# spin_pov_LDO.net
KiCad netlist of a schematic drawn in EAGLE
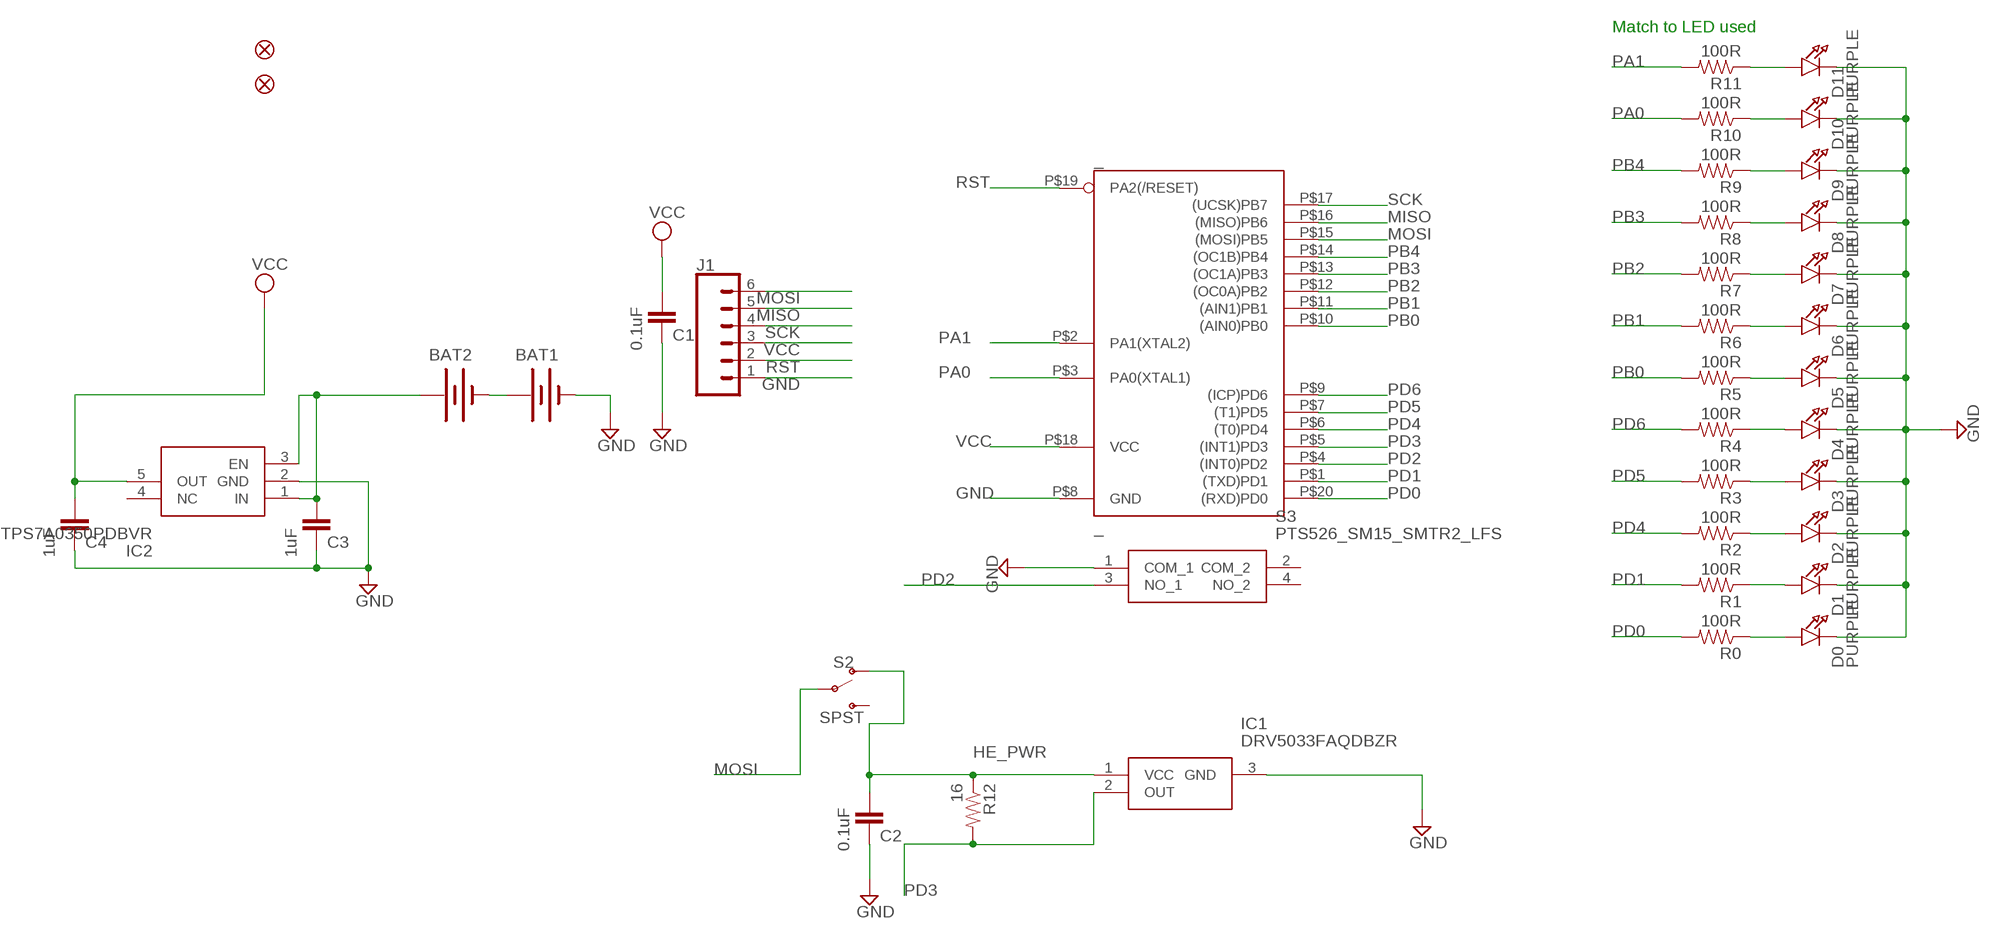
[diagram p0: schematic, sheet 1]

(export (version "E")
  (design (tool "Eeschema 10.0.6"))
  (components
    (comp (ref "AFID1")
      (value "FIDUCIAL\"\"")
      (footprint "eagle-import:FIDUCIAL_1MM")
      (libsource (lib "eagle-import") (part "FIDUCIAL{dblquote}{dblquote}"))
    )
    (comp (ref "AFID2")
      (value "FIDUCIAL\"\"")
      (footprint "eagle-import:FIDUCIAL_1MM")
      (libsource (lib "eagle-import") (part "FIDUCIAL{dblquote}{dblquote}"))
    )
    (comp (ref "BAT1")
      (value "SPARKFUN_BATTERYSPARKFUN_BATTCOMM_20MM_LINX")
      (footprint "eagle-import:SPARKFUN_BATTCOM_20MM_LINX")
      (libsource (lib "eagle-import") (part "SPARKFUN_BATTERYSPARKFUN_BATTCOMM_20MM_LINX"))
    )
    (comp (ref "BAT2")
      (value "SPARKFUN_BATTERYSPARKFUN_BATTCOMM_20MM_LINX")
      (footprint "eagle-import:SPARKFUN_BATTCOM_20MM_LINX")
      (libsource (lib "eagle-import") (part "SPARKFUN_BATTERYSPARKFUN_BATTCOMM_20MM_LINX"))
    )
    (comp (ref "C1")
      (value "0.1uF")
      (footprint "eagle-import:0805")
      (libsource (lib "eagle-import") (part "CAP0805"))
    )
    (comp (ref "C2")
      (value "0.1uF")
      (footprint "eagle-import:0805")
      (libsource (lib "eagle-import") (part "CAP0805"))
    )
    (comp (ref "C3")
      (value "1uF")
      (footprint "eagle-import:0805")
      (libsource (lib "eagle-import") (part "CAP0805"))
    )
    (comp (ref "C4")
      (value "1uF")
      (footprint "eagle-import:0805")
      (libsource (lib "eagle-import") (part "CAP0805"))
    )
    (comp (ref "D0")
      (value "PURPLE")
      (footprint "eagle-import:CHIPLED_0805_NOOUTLINE")
      (libsource (lib "eagle-import") (part "LED0805_NOOUTLINE"))
    )
    (comp (ref "D1")
      (value "PURPLE")
      (footprint "eagle-import:CHIPLED_0805_NOOUTLINE")
      (libsource (lib "eagle-import") (part "LED0805_NOOUTLINE"))
    )
    (comp (ref "D2")
      (value "PURPLE")
      (footprint "eagle-import:CHIPLED_0805_NOOUTLINE")
      (libsource (lib "eagle-import") (part "LED0805_NOOUTLINE"))
    )
    (comp (ref "D3")
      (value "PURPLE")
      (footprint "eagle-import:CHIPLED_0805_NOOUTLINE")
      (libsource (lib "eagle-import") (part "LED0805_NOOUTLINE"))
    )
    (comp (ref "D4")
      (value "PURPLE")
      (footprint "eagle-import:CHIPLED_0805_NOOUTLINE")
      (libsource (lib "eagle-import") (part "LED0805_NOOUTLINE"))
    )
    (comp (ref "D5")
      (value "PURPLE")
      (footprint "eagle-import:CHIPLED_0805_NOOUTLINE")
      (libsource (lib "eagle-import") (part "LED0805_NOOUTLINE"))
    )
    (comp (ref "D6")
      (value "PURPLE")
      (footprint "eagle-import:CHIPLED_0805_NOOUTLINE")
      (libsource (lib "eagle-import") (part "LED0805_NOOUTLINE"))
    )
    (comp (ref "D7")
      (value "PURPLE")
      (footprint "eagle-import:CHIPLED_0805_NOOUTLINE")
      (libsource (lib "eagle-import") (part "LED0805_NOOUTLINE"))
    )
    (comp (ref "D8")
      (value "PURPLE")
      (footprint "eagle-import:CHIPLED_0805_NOOUTLINE")
      (libsource (lib "eagle-import") (part "LED0805_NOOUTLINE"))
    )
    (comp (ref "D9")
      (value "PURPLE")
      (footprint "eagle-import:CHIPLED_0805_NOOUTLINE")
      (libsource (lib "eagle-import") (part "LED0805_NOOUTLINE"))
    )
    (comp (ref "D10")
      (value "PURPLE")
      (footprint "eagle-import:CHIPLED_0805_NOOUTLINE")
      (libsource (lib "eagle-import") (part "LED0805_NOOUTLINE"))
    )
    (comp (ref "D11")
      (value "PURPLE")
      (footprint "eagle-import:CHIPLED_0805_NOOUTLINE")
      (libsource (lib "eagle-import") (part "LED0805_NOOUTLINE"))
    )
    (comp (ref "IC1")
      (value "DRV5033FAQDBZR")
      (footprint "eagle-import:SOT95P237X112-3N")
      (fields (field (name "MOUSER_PART_NUMBER") "595-DRV5033FAQDBZR"))
      (libsource (lib "eagle-import") (part "DRV5033FAQDBZR"))
    )
    (comp (ref "IC2")
      (value "TPS7A0350PDBVR")
      (footprint "eagle-import:SOT95P280X145-5N")
      (fields (field (name "MOUSER_PART_NUMBER") "595-TPS7A0350PDBVR"))
      (libsource (lib "eagle-import") (part "TPS7A0350PDBVR"))
    )
    (comp (ref "J1")
      (value "CONN_06SMD-FEMALE-V2")
      (footprint "eagle-import:1X06-SMD-FEMALE")
      (libsource (lib "eagle-import") (part "CONN_06SMD-FEMALE-V2"))
    )
    (comp (ref "R0")
      (value "100R")
      (footprint "eagle-import:0805")
      (fields (field (name "SPICEPREFIX") "R"))
      (libsource (lib "eagle-import") (part "RESISTOR"))
    )
    (comp (ref "R1")
      (value "100R")
      (footprint "eagle-import:0805")
      (libsource (lib "eagle-import") (part "RESISTOR"))
    )
    (comp (ref "R2")
      (value "100R")
      (footprint "eagle-import:0805")
      (libsource (lib "eagle-import") (part "RESISTOR"))
    )
    (comp (ref "R3")
      (value "100R")
      (footprint "eagle-import:0805")
      (libsource (lib "eagle-import") (part "RESISTOR"))
    )
    (comp (ref "R4")
      (value "100R")
      (footprint "eagle-import:0805")
      (libsource (lib "eagle-import") (part "RESISTOR"))
    )
    (comp (ref "R5")
      (value "100R")
      (footprint "eagle-import:0805")
      (libsource (lib "eagle-import") (part "RESISTOR"))
    )
    (comp (ref "R6")
      (value "100R")
      (footprint "eagle-import:0805")
      (libsource (lib "eagle-import") (part "RESISTOR"))
    )
    (comp (ref "R7")
      (value "100R")
      (footprint "eagle-import:0805")
      (libsource (lib "eagle-import") (part "RESISTOR"))
    )
    (comp (ref "R8")
      (value "100R")
      (footprint "eagle-import:0805")
      (libsource (lib "eagle-import") (part "RESISTOR"))
    )
    (comp (ref "R9")
      (value "100R")
      (footprint "eagle-import:0805")
      (libsource (lib "eagle-import") (part "RESISTOR"))
    )
    (comp (ref "R10")
      (value "100R")
      (footprint "eagle-import:0805")
      (libsource (lib "eagle-import") (part "RESISTOR"))
    )
    (comp (ref "R11")
      (value "100R")
      (footprint "eagle-import:0805")
      (libsource (lib "eagle-import") (part "RESISTOR"))
    )
    (comp (ref "R12")
      (value "16")
      (footprint "eagle-import:0805")
      (libsource (lib "eagle-import") (part "RESISTOR"))
    )
    (comp (ref "S2")
      (value "SPST")
      (footprint "eagle-import:SWITCH_SPST_SMD_A")
      (libsource (lib "eagle-import") (part "SWITCH-SPDT-SMD-RIGHT-ANGLE"))
    )
    (comp (ref "S3")
      (value "PTS526_SM15_SMTR2_LFS")
      (footprint "eagle-import:PTS526SM15SMTR2LFS")
      (fields
        (field (name "MANUFACTURER_PART_NUMBER") "PTS526 SM15 SMTR2 LFS")
        (field (name "MOUSER_PART_NUMBER") "611-PTS526SM15SMTR2L")
      )
      (libsource (lib "eagle-import") (part "PTS526_SM15_SMTR2_LFS"))
    )
    (comp (ref "_")
      (value "_")
      (footprint "eagle-import:MLF20")
      (libsource (lib "eagle-import") (part "TINY2313-M"))
    )
  )
  (nets
    (net (code "1") (name "/HE_PWR") (class "Default")
      (node (ref "C2") (pin "1") (pinfunction "1_1") (pintype "passive"))
      (node (ref "IC1") (pin "1") (pinfunction "VCC_1") (pintype "bidirectional"))
      (node (ref "R12") (pin "1") (pinfunction "1_1") (pintype "passive"))
      (node (ref "S2") (pin "1") (pinfunction "O_1") (pintype "passive"))
    )
    (net (code "2") (name "/MISO") (class "Default")
      (node (ref "J1") (pin "5") (pinfunction "5_5") (pintype "passive"))
      (node (ref "_") (pin "P$16") (pinfunction "(MISO)PB6_P$16") (pintype "bidirectional"))
    )
    (net (code "3") (name "/MOSI") (class "Default")
      (node (ref "J1") (pin "6") (pinfunction "6_6") (pintype "passive"))
      (node (ref "S2") (pin "2") (pinfunction "P_2") (pintype "passive"))
      (node (ref "_") (pin "P$15") (pinfunction "(MOSI)PB5_P$15") (pintype "bidirectional"))
    )
    (net (code "4") (name "/PA0") (class "Default")
      (node (ref "R10") (pin "2") (pinfunction "2_2") (pintype "passive"))
      (node (ref "_") (pin "P$3") (pinfunction "PA0(XTAL1)_P$3") (pintype "bidirectional"))
    )
    (net (code "5") (name "/PA1") (class "Default")
      (node (ref "R11") (pin "2") (pinfunction "2_2") (pintype "passive"))
      (node (ref "_") (pin "P$2") (pinfunction "PA1(XTAL2)_P$2") (pintype "bidirectional"))
    )
    (net (code "6") (name "/PB0") (class "Default")
      (node (ref "R5") (pin "2") (pinfunction "2_2") (pintype "passive"))
      (node (ref "_") (pin "P$10") (pinfunction "(AIN0)PB0_P$10") (pintype "bidirectional"))
    )
    (net (code "7") (name "/PB1") (class "Default")
      (node (ref "R6") (pin "2") (pinfunction "2_2") (pintype "passive"))
      (node (ref "_") (pin "P$11") (pinfunction "(AIN1)PB1_P$11") (pintype "bidirectional"))
    )
    (net (code "8") (name "/PB2") (class "Default")
      (node (ref "R7") (pin "2") (pinfunction "2_2") (pintype "passive"))
      (node (ref "_") (pin "P$12") (pinfunction "(OC0A)PB2_P$12") (pintype "bidirectional"))
    )
    (net (code "9") (name "/PB3") (class "Default")
      (node (ref "R8") (pin "2") (pinfunction "2_2") (pintype "passive"))
      (node (ref "_") (pin "P$13") (pinfunction "(OC1A)PB3_P$13") (pintype "bidirectional"))
    )
    (net (code "10") (name "/PB4") (class "Default")
      (node (ref "R9") (pin "2") (pinfunction "2_2") (pintype "passive"))
      (node (ref "_") (pin "P$14") (pinfunction "(OC1B)PB4_P$14") (pintype "bidirectional"))
    )
    (net (code "11") (name "/PD0") (class "Default")
      (node (ref "R0") (pin "2") (pinfunction "2_2") (pintype "passive"))
      (node (ref "_") (pin "P$20") (pinfunction "(RXD)PD0_P$20") (pintype "bidirectional"))
    )
    (net (code "12") (name "/PD1") (class "Default")
      (node (ref "R1") (pin "2") (pinfunction "2_2") (pintype "passive"))
      (node (ref "_") (pin "P$1") (pinfunction "(TXD)PD1_P$1") (pintype "bidirectional"))
    )
    (net (code "13") (name "/PD2") (class "Default")
      (node (ref "S3") (pin "3") (pinfunction "NO_1_3") (pintype "bidirectional"))
      (node (ref "_") (pin "P$4") (pinfunction "(INT0)PD2_P$4") (pintype "bidirectional"))
    )
    (net (code "14") (name "/PD3") (class "Default")
      (node (ref "IC1") (pin "2") (pinfunction "OUT_2") (pintype "bidirectional"))
      (node (ref "R12") (pin "2") (pinfunction "2_2") (pintype "passive"))
      (node (ref "_") (pin "P$5") (pinfunction "(INT1)PD3_P$5") (pintype "bidirectional"))
    )
    (net (code "15") (name "/PD4") (class "Default")
      (node (ref "R2") (pin "2") (pinfunction "2_2") (pintype "passive"))
      (node (ref "_") (pin "P$6") (pinfunction "(T0)PD4_P$6") (pintype "bidirectional"))
    )
    (net (code "16") (name "/PD5") (class "Default")
      (node (ref "R3") (pin "2") (pinfunction "2_2") (pintype "passive"))
      (node (ref "_") (pin "P$7") (pinfunction "(T1)PD5_P$7") (pintype "bidirectional"))
    )
    (net (code "17") (name "/PD6") (class "Default")
      (node (ref "R4") (pin "2") (pinfunction "2_2") (pintype "passive"))
      (node (ref "_") (pin "P$9") (pinfunction "(ICP)PD6_P$9") (pintype "bidirectional"))
    )
    (net (code "18") (name "/RST") (class "Default")
      (node (ref "J1") (pin "2") (pinfunction "2_2") (pintype "passive"))
      (node (ref "_") (pin "P$19") (pinfunction "PA2(/RESET)_P$19") (pintype "input"))
    )
    (net (code "19") (name "/SCK") (class "Default")
      (node (ref "J1") (pin "4") (pinfunction "4_4") (pintype "passive"))
      (node (ref "_") (pin "P$17") (pinfunction "(UCSK)PB7_P$17") (pintype "bidirectional"))
    )
    (net (code "20") (name "GND") (class "Default")
      (node (ref "BAT1") (pin "2") (pinfunction "-_2") (pintype "power_in"))
      (node (ref "C1") (pin "2") (pinfunction "2_2") (pintype "passive"))
      (node (ref "C2") (pin "2") (pinfunction "2_2") (pintype "passive"))
      (node (ref "C3") (pin "2") (pinfunction "2_2") (pintype "passive"))
      (node (ref "C4") (pin "2") (pinfunction "2_2") (pintype "passive"))
      (node (ref "D0") (pin "C") (pinfunction "C_C") (pintype "passive"))
      (node (ref "D1") (pin "C") (pinfunction "C_C") (pintype "passive"))
      (node (ref "D10") (pin "C") (pinfunction "C_C") (pintype "passive"))
      (node (ref "D11") (pin "C") (pinfunction "C_C") (pintype "passive"))
      (node (ref "D2") (pin "C") (pinfunction "C_C") (pintype "passive"))
      (node (ref "D3") (pin "C") (pinfunction "C_C") (pintype "passive"))
      (node (ref "D4") (pin "C") (pinfunction "C_C") (pintype "passive"))
      (node (ref "D5") (pin "C") (pinfunction "C_C") (pintype "passive"))
      (node (ref "D6") (pin "C") (pinfunction "C_C") (pintype "passive"))
      (node (ref "D7") (pin "C") (pinfunction "C_C") (pintype "passive"))
      (node (ref "D8") (pin "C") (pinfunction "C_C") (pintype "passive"))
      (node (ref "D9") (pin "C") (pinfunction "C_C") (pintype "passive"))
      (node (ref "IC1") (pin "3") (pinfunction "GND_3") (pintype "bidirectional"))
      (node (ref "IC2") (pin "2") (pinfunction "GND_2") (pintype "bidirectional"))
      (node (ref "J1") (pin "1") (pinfunction "1_1") (pintype "passive"))
      (node (ref "S3") (pin "1") (pinfunction "COM_1_1") (pintype "bidirectional"))
      (node (ref "_") (pin "P$8") (pinfunction "GND_P$8") (pintype "power_in"))
    )
    (net (code "21") (name "Net-(BAT1-+)") (class "Default")
      (node (ref "BAT1") (pin "1") (pinfunction "+_1") (pintype "power_in"))
      (node (ref "BAT2") (pin "2") (pinfunction "-_2") (pintype "power_in"))
    )
    (net (code "22") (name "Net-(BAT2-+)") (class "Default")
      (node (ref "BAT2") (pin "1") (pinfunction "+_1") (pintype "power_in"))
      (node (ref "C3") (pin "1") (pinfunction "1_1") (pintype "passive"))
      (node (ref "IC2") (pin "1") (pinfunction "IN_1") (pintype "bidirectional"))
      (node (ref "IC2") (pin "3") (pinfunction "EN_3") (pintype "bidirectional"))
    )
    (net (code "23") (name "Net-(D0-PadA)") (class "Default")
      (node (ref "D0") (pin "A") (pinfunction "A_A") (pintype "passive"))
      (node (ref "R0") (pin "1") (pinfunction "1_1") (pintype "passive"))
    )
    (net (code "24") (name "Net-(D1-PadA)") (class "Default")
      (node (ref "D1") (pin "A") (pinfunction "A_A") (pintype "passive"))
      (node (ref "R1") (pin "1") (pinfunction "1_1") (pintype "passive"))
    )
    (net (code "25") (name "Net-(D2-PadA)") (class "Default")
      (node (ref "D2") (pin "A") (pinfunction "A_A") (pintype "passive"))
      (node (ref "R2") (pin "1") (pinfunction "1_1") (pintype "passive"))
    )
    (net (code "26") (name "Net-(D3-PadA)") (class "Default")
      (node (ref "D3") (pin "A") (pinfunction "A_A") (pintype "passive"))
      (node (ref "R3") (pin "1") (pinfunction "1_1") (pintype "passive"))
    )
    (net (code "27") (name "Net-(D4-PadA)") (class "Default")
      (node (ref "D4") (pin "A") (pinfunction "A_A") (pintype "passive"))
      (node (ref "R4") (pin "1") (pinfunction "1_1") (pintype "passive"))
    )
    (net (code "28") (name "Net-(D5-PadA)") (class "Default")
      (node (ref "D5") (pin "A") (pinfunction "A_A") (pintype "passive"))
      (node (ref "R5") (pin "1") (pinfunction "1_1") (pintype "passive"))
    )
    (net (code "29") (name "Net-(D6-PadA)") (class "Default")
      (node (ref "D6") (pin "A") (pinfunction "A_A") (pintype "passive"))
      (node (ref "R6") (pin "1") (pinfunction "1_1") (pintype "passive"))
    )
    (net (code "30") (name "Net-(D7-PadA)") (class "Default")
      (node (ref "D7") (pin "A") (pinfunction "A_A") (pintype "passive"))
      (node (ref "R7") (pin "1") (pinfunction "1_1") (pintype "passive"))
    )
    (net (code "31") (name "Net-(D8-PadA)") (class "Default")
      (node (ref "D8") (pin "A") (pinfunction "A_A") (pintype "passive"))
      (node (ref "R8") (pin "1") (pinfunction "1_1") (pintype "passive"))
    )
    (net (code "32") (name "Net-(D9-PadA)") (class "Default")
      (node (ref "D9") (pin "A") (pinfunction "A_A") (pintype "passive"))
      (node (ref "R9") (pin "1") (pinfunction "1_1") (pintype "passive"))
    )
    (net (code "33") (name "Net-(D10-PadA)") (class "Default")
      (node (ref "D10") (pin "A") (pinfunction "A_A") (pintype "passive"))
      (node (ref "R10") (pin "1") (pinfunction "1_1") (pintype "passive"))
    )
    (net (code "34") (name "Net-(D11-PadA)") (class "Default")
      (node (ref "D11") (pin "A") (pinfunction "A_A") (pintype "passive"))
      (node (ref "R11") (pin "1") (pinfunction "1_1") (pintype "passive"))
    )
    (net (code "35") (name "VCC") (class "Default")
      (node (ref "C1") (pin "1") (pinfunction "1_1") (pintype "passive"))
      (node (ref "C4") (pin "1") (pinfunction "1_1") (pintype "passive"))
      (node (ref "IC2") (pin "5") (pinfunction "OUT_5") (pintype "bidirectional"))
      (node (ref "J1") (pin "3") (pinfunction "3_3") (pintype "passive"))
      (node (ref "_") (pin "P$18") (pinfunction "VCC_P$18") (pintype "power_in"))
    )
    (net (code "36") (name "unconnected-(IC2-NC-Pad4)") (class "Default")
      (node (ref "IC2") (pin "4") (pinfunction "NC_4") (pintype "no_connect"))
    )
    (net (code "37") (name "unconnected-(S2-S-Pad3)") (class "Default")
      (node (ref "S2") (pin "3") (pinfunction "S_3") (pintype "passive"))
    )
    (net (code "38") (name "unconnected-(S3-COM_2-Pad2)") (class "Default")
      (node (ref "S3") (pin "2") (pinfunction "COM_2_2") (pintype "bidirectional"))
    )
    (net (code "39") (name "unconnected-(S3-NO_2-Pad4)") (class "Default")
      (node (ref "S3") (pin "4") (pinfunction "NO_2_4") (pintype "bidirectional"))
    )
  )
)
